# MotorCell.net
KiCad netlist of a schematic drawn in Altium Designer
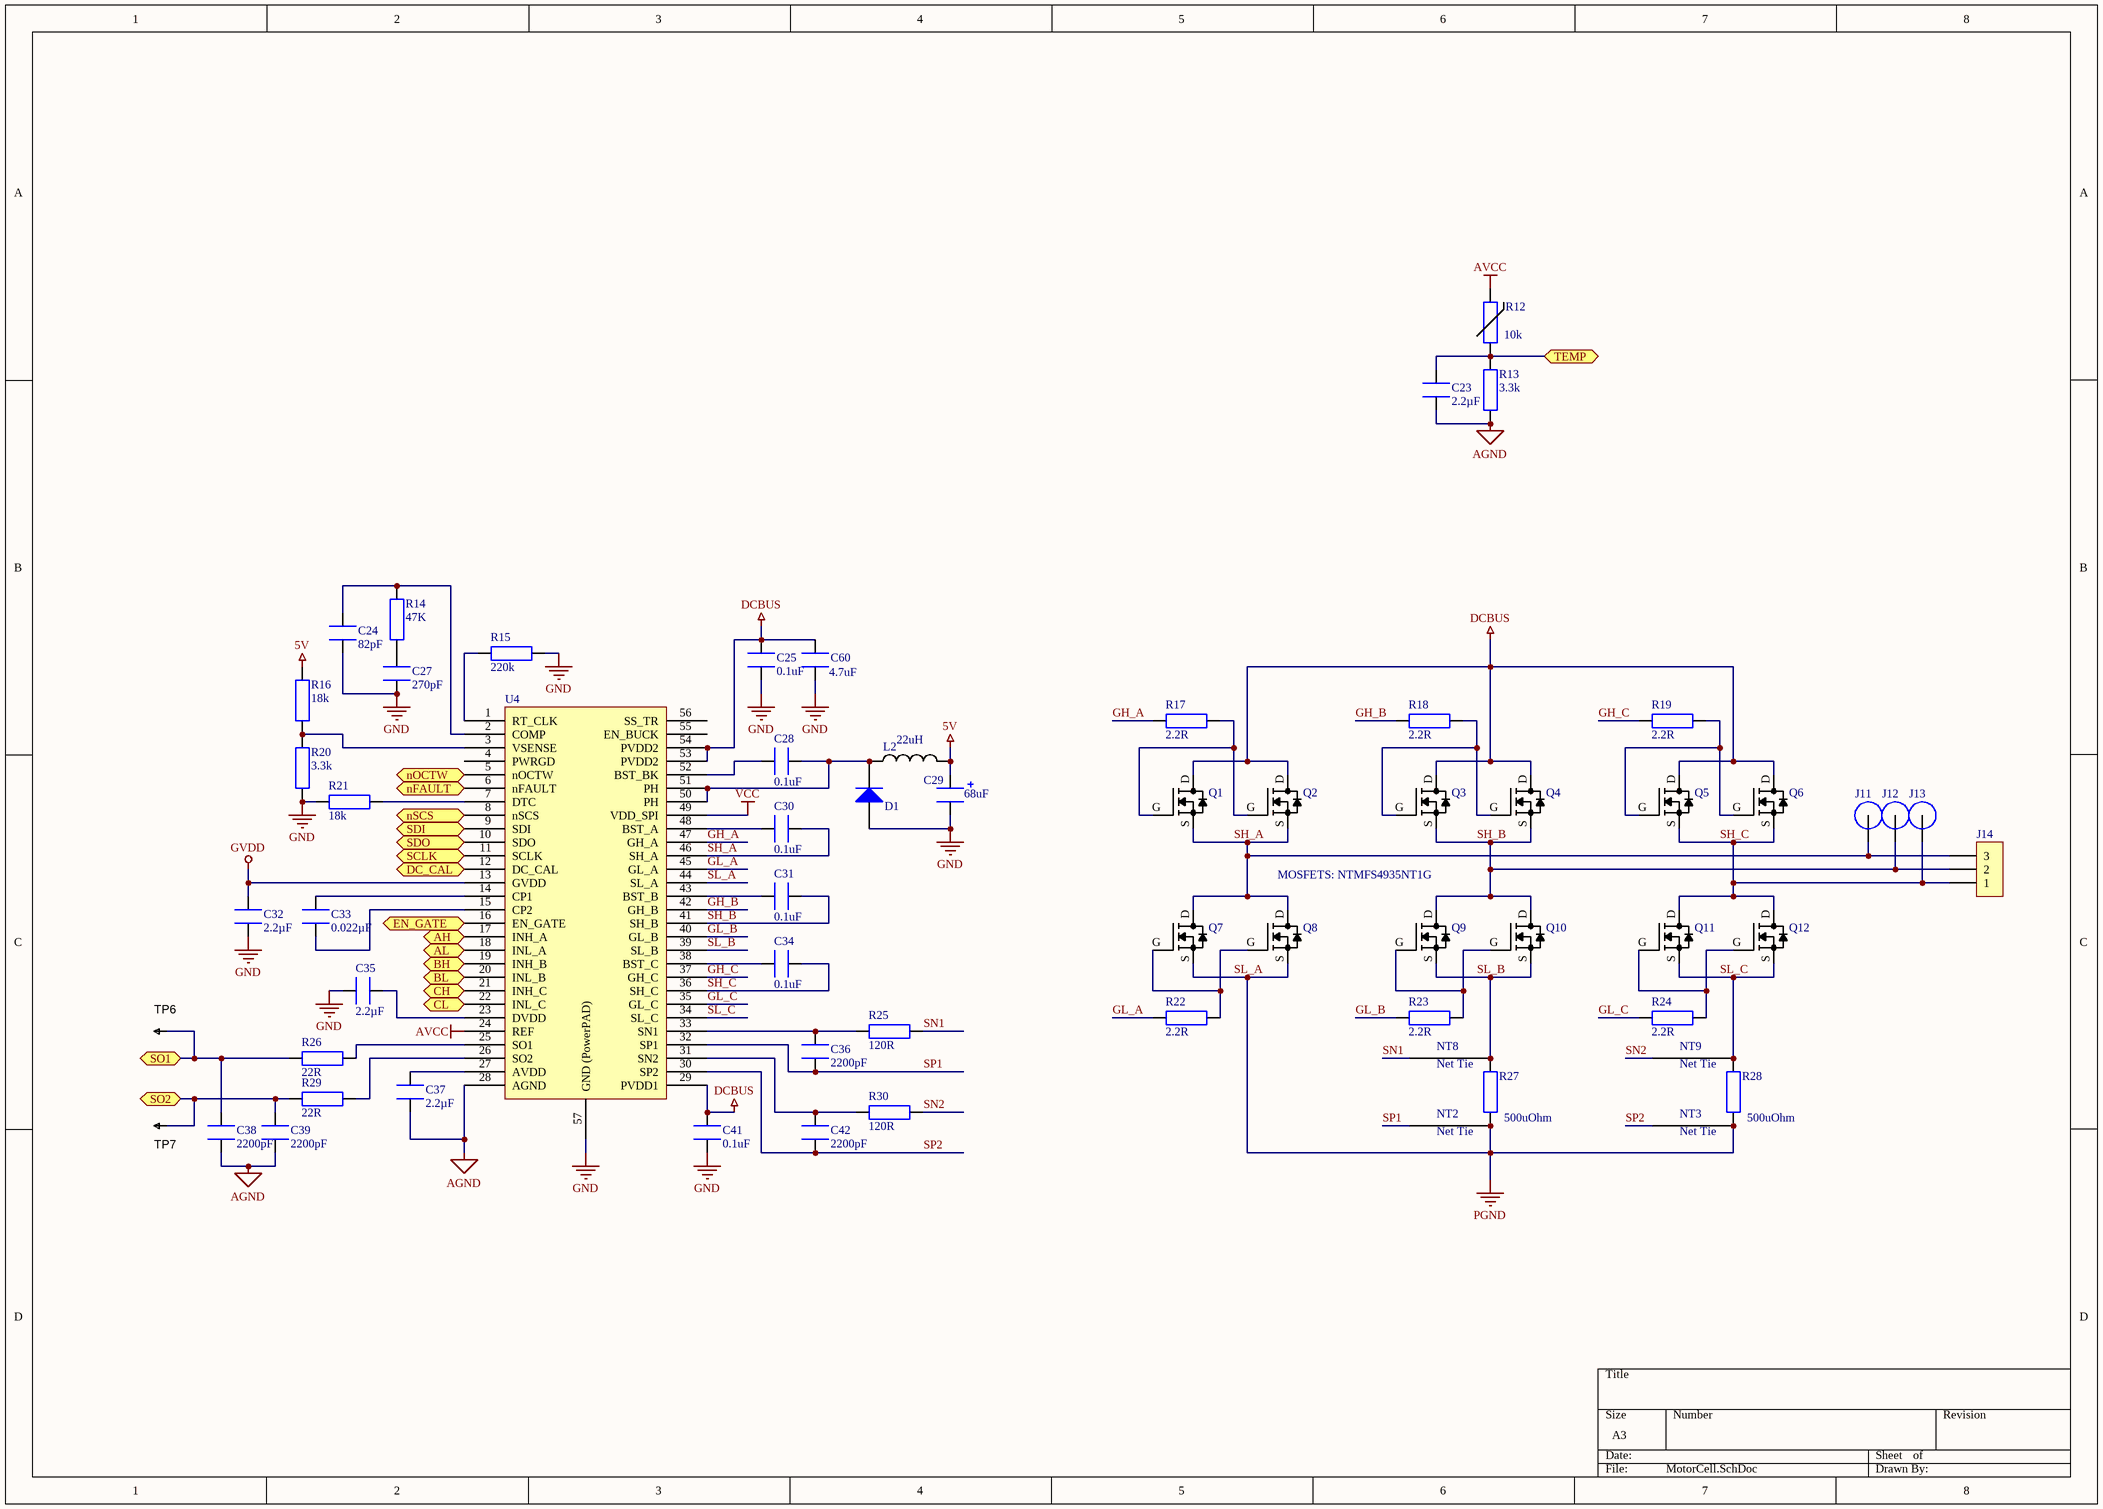
[diagram p0: MotorCell.SchDoc]

(export (version "E")
  (design (tool "Eeschema 10.0.6"))
  (components
    (comp (ref "C23")
      (value "2.2µF")
      (footprint "CAPC1608X09L")
      (description "CAP CER 2.2UF 16V X5R 0603")
      (fields
        (field (name "MANUFACTURER") "Murata Electronics North America")
        (field (name "MANUFACTURER PART NUMBER") "GRM188R61C225KE15D")
      )
      (libsource (lib "CustomComponents") (part "GRM188R61C225KE15D"))
    )
    (comp (ref "C24")
      (value "82pF")
      (footprint "CAPC1608X09L")
      (description "CAP CER 82PF 100V NP0 0603")
      (fields
        (field (name "MANUFACTURER") "Murata Electronics North America")
        (field (name "MANUFACTURER PART NUMBER") "GRM1885C2A820JA01D")
      )
      (libsource (lib "CustomComponents") (part "GRM1885C2A820JA01D"))
    )
    (comp (ref "C25")
      (value "0.1uF")
      (footprint "CAPC1608X09L")
      (description "CAP CER 0.1UF 50V X7R 0603")
      (fields
        (field (name "MANUFACTURER") "Murata Electronics North America")
        (field (name "MANUFACTURER PART NUMBER") "GRM188R71H104KA93D")
      )
      (libsource (lib "CustomComponents") (part "GRM188R71H104KA93D"))
    )
    (comp (ref "C27")
      (value "270pF")
      (footprint "CAPC1608X09L")
      (description "CAP CER 270PF 50V NP0 0603")
      (fields
        (field (name "MANUFACTURER") "Murata Electronics North America")
        (field (name "MANUFACTURER PART NUMBER") "GRM1885C1H271JA01D")
      )
      (libsource (lib "CustomComponents") (part "GRM1885C1H271JA01D"))
    )
    (comp (ref "C28")
      (value "0.1uF")
      (footprint "CAPC1608X09L")
      (description "CAP CER 0.1UF 50V X7R 0603")
      (fields
        (field (name "MANUFACTURER") "Murata Electronics North America")
        (field (name "MANUFACTURER PART NUMBER") "GRM188R71H104KA93D")
      )
      (libsource (lib "CustomComponents") (part "GRM188R71H104KA93D"))
    )
    (comp (ref "C29")
      (value "68uF")
      (footprint "CAPCP6032X28N")
      (description "CAP TANT 68UF 16V 20% 2312 250mOhm")
      (fields (field (name "MANUFACTURER") "KEMET") (field (name "TOLERANCE") "±20%"))
      (libsource (lib "CustomComponents") (part "T495C686M016ATE250"))
    )
    (comp (ref "C30")
      (value "0.1uF")
      (footprint "CAPC1608X09L")
      (description "CAP CER 0.1UF 50V X7R 0603")
      (fields
        (field (name "MANUFACTURER") "Murata Electronics North America")
        (field (name "MANUFACTURER PART NUMBER") "GRM188R71H104KA93D")
      )
      (libsource (lib "CustomComponents") (part "GRM188R71H104KA93D"))
    )
    (comp (ref "C31")
      (value "0.1uF")
      (footprint "CAPC1608X09L")
      (description "CAP CER 0.1UF 50V X7R 0603")
      (fields
        (field (name "MANUFACTURER") "Murata Electronics North America")
        (field (name "MANUFACTURER PART NUMBER") "GRM188R71H104KA93D")
      )
      (libsource (lib "CustomComponents") (part "GRM188R71H104KA93D"))
    )
    (comp (ref "C32")
      (value "2.2µF")
      (footprint "CAPC1608X09L")
      (description "CAP CER 2.2UF 16V X5R 0603")
      (fields
        (field (name "MANUFACTURER") "Murata Electronics North America")
        (field (name "MANUFACTURER PART NUMBER") "GRM188R61C225KE15D")
      )
      (libsource (lib "CustomComponents") (part "GRM188R61C225KE15D"))
    )
    (comp (ref "C33")
      (value "0.022µF")
      (footprint "CAPC1608X09L")
      (description "CAP CER 0.022UF 50V X7R 0603")
      (fields
        (field (name "MANUFACTURER") "Murata Electronics North America")
        (field (name "MANUFACTURER PART NUMBER") "GRM188R71H223KA01D")
      )
      (libsource (lib "CustomComponents") (part "GRM188R71H223KA01D"))
    )
    (comp (ref "C34")
      (value "0.1uF")
      (footprint "CAPC1608X09L")
      (description "CAP CER 0.1UF 50V X7R 0603")
      (fields
        (field (name "MANUFACTURER") "Murata Electronics North America")
        (field (name "MANUFACTURER PART NUMBER") "GRM188R71H104KA93D")
      )
      (libsource (lib "CustomComponents") (part "GRM188R71H104KA93D"))
    )
    (comp (ref "C35")
      (value "2.2µF")
      (footprint "CAPC1608X09L")
      (description "CAP CER 2.2UF 16V X5R 0603")
      (fields
        (field (name "MANUFACTURER") "Murata Electronics North America")
        (field (name "MANUFACTURER PART NUMBER") "GRM188R61C225KE15D")
      )
      (libsource (lib "CustomComponents") (part "GRM188R61C225KE15D"))
    )
    (comp (ref "C36")
      (value "2200pF")
      (footprint "CAPC1608X09L")
      (description "CAP CER 2200PF 50V NP0 0603")
      (fields
        (field (name "MANUFACTURER") "Murata Electronics North America")
        (field (name "TOLERANCE") "±5%")
      )
      (libsource (lib "CustomComponents") (part "GRM1885C1H222JA01D"))
    )
    (comp (ref "C37")
      (value "2.2µF")
      (footprint "CAPC1608X09L")
      (description "CAP CER 2.2UF 16V X5R 0603")
      (fields
        (field (name "MANUFACTURER") "Murata Electronics North America")
        (field (name "MANUFACTURER PART NUMBER") "GRM188R61C225KE15D")
      )
      (libsource (lib "CustomComponents") (part "GRM188R61C225KE15D"))
    )
    (comp (ref "C38")
      (value "2200pF")
      (footprint "CAPC1608X09L")
      (description "CAP CER 2200PF 50V NP0 0603")
      (fields
        (field (name "MANUFACTURER") "Murata Electronics North America")
        (field (name "TOLERANCE") "±5%")
      )
      (libsource (lib "CustomComponents") (part "GRM1885C1H222JA01D"))
    )
    (comp (ref "C39")
      (value "2200pF")
      (footprint "CAPC1608X09L")
      (description "CAP CER 2200PF 50V NP0 0603")
      (fields
        (field (name "MANUFACTURER") "Murata Electronics North America")
        (field (name "TOLERANCE") "±5%")
      )
      (libsource (lib "CustomComponents") (part "GRM1885C1H222JA01D"))
    )
    (comp (ref "C41")
      (value "0.1uF")
      (footprint "CAPC1608X09L")
      (description "CAP CER 0.1UF 50V X7R 0603")
      (fields
        (field (name "MANUFACTURER") "Murata Electronics North America")
        (field (name "MANUFACTURER PART NUMBER") "GRM188R71H104KA93D")
      )
      (libsource (lib "CustomComponents") (part "GRM188R71H104KA93D"))
    )
    (comp (ref "C42")
      (value "2200pF")
      (footprint "CAPC1608X09L")
      (description "CAP CER 2200PF 50V NP0 0603")
      (fields
        (field (name "MANUFACTURER") "Murata Electronics North America")
        (field (name "TOLERANCE") "±5%")
      )
      (libsource (lib "CustomComponents") (part "GRM1885C1H222JA01D"))
    )
    (comp (ref "C60")
      (value "4.7uF")
      (footprint "CAPC2012X09N")
      (description "CAP CER 4.7UF 35V X5R 0805")
      (fields
        (field (name "MANUFACTURER") "Murata Electronics North America")
        (field (name "TOLERANCE") "±10%")
      )
      (libsource (lib "CustomComponents") (part "GRM219R6YA475KA73D"))
    )
    (comp (ref "D1")
      (value "~")
      (footprint "DIOM2717X10N")
      (description "Rectifier Diode, Single, 40 V, 1 A, SOD-123FL, 2, 550 mV")
      (libsource (lib "CustomComponents") (part "MBR140SFT1G"))
    )
    (comp (ref "J11")
      (value "~")
      (footprint "M3 Spade Hole")
      (description "M3 Spade Terminal")
      (libsource (lib "CustomComponents") (part "M3 Spade Terminal"))
    )
    (comp (ref "J12")
      (value "~")
      (footprint "M3 Spade Hole")
      (description "M3 Spade Terminal")
      (libsource (lib "CustomComponents") (part "M3 Spade Terminal"))
    )
    (comp (ref "J13")
      (value "~")
      (footprint "M3 Spade Hole")
      (description "M3 Spade Terminal")
      (libsource (lib "CustomComponents") (part "M3 Spade Terminal"))
    )
    (comp (ref "J14")
      (value "1704936")
      (footprint "1704936")
      (description "CONN TERM BLOCK 3POS 7.62MM")
      (fields (field (name "MANUFACTURER") "Phoenix Contact") (field (name "VOLTAGE") "300V"))
      (libsource (lib "CustomComponents") (part "1704936"))
    )
    (comp (ref "L2")
      (value "22uH")
      (footprint "INDC6060X28N")
      (description "INDUCTOR 22UH 1.4A 175.5 MOHM")
      (libsource (lib "CustomComponents") (part "NR6028T220M"))
    )
    (comp (ref "NT2")
      (value "0.25mm")
      (footprint "NetTie_0.25mm")
      (libsource (lib "CustomComponents") (part "NetTie_0.25mm"))
    )
    (comp (ref "NT3")
      (value "0.25mm")
      (footprint "NetTie_0.25mm")
      (libsource (lib "CustomComponents") (part "NetTie_0.25mm"))
    )
    (comp (ref "NT8")
      (value "0.25mm")
      (footprint "NetTie_0.25mm")
      (libsource (lib "CustomComponents") (part "NetTie_0.25mm"))
    )
    (comp (ref "NT9")
      (value "0.25mm")
      (footprint "NetTie_0.25mm")
      (libsource (lib "CustomComponents") (part "NetTie_0.25mm"))
    )
    (comp (ref "Q1")
      (value "~")
      (footprint "SO8FL")
      (description "MOSFET N-CH 30V 13A SO8FL")
      (fields
        (field (name "MANUFACTURER") "ON Semiconductor")
        (field (name "MANUFACTURER PART NUMBER") "NTMFS4935NT1G")
      )
      (libsource (lib "CustomComponents") (part "NTMFS4935NT1G"))
    )
    (comp (ref "Q2")
      (value "FILL_FOOTPRINT")
      (footprint "SO8FL_FILL")
      (description "MOSFET N-CH 30V 13A SO8FL")
      (fields
        (field (name "MANUFACTURER") "ON Semiconductor")
        (field (name "MANUFACTURER PART NUMBER") "NTMFS4935NT1G")
      )
      (libsource (lib "CustomComponents") (part "NTMFS4935NT1G"))
    )
    (comp (ref "Q3")
      (value "~")
      (footprint "SO8FL")
      (description "MOSFET N-CH 30V 13A SO8FL")
      (fields
        (field (name "MANUFACTURER") "ON Semiconductor")
        (field (name "MANUFACTURER PART NUMBER") "NTMFS4935NT1G")
      )
      (libsource (lib "CustomComponents") (part "NTMFS4935NT1G"))
    )
    (comp (ref "Q4")
      (value "FILL_FOOTPRINT")
      (footprint "SO8FL_FILL")
      (description "MOSFET N-CH 30V 13A SO8FL")
      (fields
        (field (name "MANUFACTURER") "ON Semiconductor")
        (field (name "MANUFACTURER PART NUMBER") "NTMFS4935NT1G")
      )
      (libsource (lib "CustomComponents") (part "NTMFS4935NT1G"))
    )
    (comp (ref "Q5")
      (value "~")
      (footprint "SO8FL")
      (description "MOSFET N-CH 30V 13A SO8FL")
      (fields
        (field (name "MANUFACTURER") "ON Semiconductor")
        (field (name "MANUFACTURER PART NUMBER") "NTMFS4935NT1G")
      )
      (libsource (lib "CustomComponents") (part "NTMFS4935NT1G"))
    )
    (comp (ref "Q6")
      (value "FILL_FOOTPRINT")
      (footprint "SO8FL_FILL")
      (description "MOSFET N-CH 30V 13A SO8FL")
      (fields
        (field (name "MANUFACTURER") "ON Semiconductor")
        (field (name "MANUFACTURER PART NUMBER") "NTMFS4935NT1G")
      )
      (libsource (lib "CustomComponents") (part "NTMFS4935NT1G"))
    )
    (comp (ref "Q7")
      (value "~")
      (footprint "SO8FL")
      (description "MOSFET N-CH 30V 13A SO8FL")
      (fields
        (field (name "MANUFACTURER") "ON Semiconductor")
        (field (name "MANUFACTURER PART NUMBER") "NTMFS4935NT1G")
      )
      (libsource (lib "CustomComponents") (part "NTMFS4935NT1G"))
    )
    (comp (ref "Q8")
      (value "~")
      (footprint "SO8FL")
      (description "MOSFET N-CH 30V 13A SO8FL")
      (fields
        (field (name "MANUFACTURER") "ON Semiconductor")
        (field (name "MANUFACTURER PART NUMBER") "NTMFS4935NT1G")
      )
      (libsource (lib "CustomComponents") (part "NTMFS4935NT1G"))
    )
    (comp (ref "Q9")
      (value "~")
      (footprint "SO8FL")
      (description "MOSFET N-CH 30V 13A SO8FL")
      (fields
        (field (name "MANUFACTURER") "ON Semiconductor")
        (field (name "MANUFACTURER PART NUMBER") "NTMFS4935NT1G")
      )
      (libsource (lib "CustomComponents") (part "NTMFS4935NT1G"))
    )
    (comp (ref "Q10")
      (value "~")
      (footprint "SO8FL")
      (description "MOSFET N-CH 30V 13A SO8FL")
      (fields
        (field (name "MANUFACTURER") "ON Semiconductor")
        (field (name "MANUFACTURER PART NUMBER") "NTMFS4935NT1G")
      )
      (libsource (lib "CustomComponents") (part "NTMFS4935NT1G"))
    )
    (comp (ref "Q11")
      (value "~")
      (footprint "SO8FL")
      (description "MOSFET N-CH 30V 13A SO8FL")
      (fields
        (field (name "MANUFACTURER") "ON Semiconductor")
        (field (name "MANUFACTURER PART NUMBER") "NTMFS4935NT1G")
      )
      (libsource (lib "CustomComponents") (part "NTMFS4935NT1G"))
    )
    (comp (ref "Q12")
      (value "~")
      (footprint "SO8FL")
      (description "MOSFET N-CH 30V 13A SO8FL")
      (fields
        (field (name "MANUFACTURER") "ON Semiconductor")
        (field (name "MANUFACTURER PART NUMBER") "NTMFS4935NT1G")
      )
      (libsource (lib "CustomComponents") (part "NTMFS4935NT1G"))
    )
    (comp (ref "R12")
      (value "10k")
      (footprint "RESC1005X40N")
      (description "THERMISTOR 10K OHM NTC 0402 SMD")
      (libsource (lib "CustomComponents") (part "NCP15XH103F03RC"))
    )
    (comp (ref "R13")
      (value "3.3k")
      (footprint "RESC1608X55N")
      (description "RES SMD 3.3K OHM 1% 1/10W 0603")
      (fields
        (field (name "MANUFACTURER") "Yageo")
        (field (name "MANUFACTURER PART NUMBER") "RC0603FR-073K3L")
      )
      (libsource (lib "CustomComponents") (part "RC0603FR-073K3L"))
    )
    (comp (ref "R14")
      (value "47K")
      (footprint "RESC1608X55N")
      (description "RES SMD 47K OHM 1% 1/10W 0603")
      (fields
        (field (name "MANUFACTURER") "Yageo")
        (field (name "MANUFACTURER PART NUMBER") "RC0603FR-0747KL")
      )
      (libsource (lib "CustomComponents") (part "RC0603FR-0747KL"))
    )
    (comp (ref "R15")
      (value "220k")
      (footprint "RESC1608X55N")
      (description "RES SMD 220K OHM 1% 1/10W 0603")
      (fields
        (field (name "MANUFACTURER") "Yageo")
        (field (name "MANUFACTURER PART NUMBER") "RC0603FR-07220KL")
      )
      (libsource (lib "CustomComponents") (part "RC0603FR-07220KL"))
    )
    (comp (ref "R16")
      (value "18k")
      (footprint "RESC1608X55N")
      (description "RES SMD 18K OHM 1% 1/10W 0603")
      (fields
        (field (name "MANUFACTURER") "Yageo")
        (field (name "MANUFACTURER PART NUMBER") "RC0603FR-0718KL")
      )
      (libsource (lib "CustomComponents") (part "RC0603FR-0718KL"))
    )
    (comp (ref "R17")
      (value "2.2R")
      (footprint "RESC1608X55N")
      (description "RES SMD 2.2 OHM 1% 1/10W 0603")
      (fields
        (field (name "MANUFACTURER") "Yageo")
        (field (name "MANUFACTURER PART NUMBER") "RC0603FR-072R2L")
      )
      (libsource (lib "CustomComponents") (part "RC0603FR-072R2L"))
    )
    (comp (ref "R18")
      (value "2.2R")
      (footprint "RESC1608X55N")
      (description "RES SMD 2.2 OHM 1% 1/10W 0603")
      (fields
        (field (name "MANUFACTURER") "Yageo")
        (field (name "MANUFACTURER PART NUMBER") "RC0603FR-072R2L")
      )
      (libsource (lib "CustomComponents") (part "RC0603FR-072R2L"))
    )
    (comp (ref "R19")
      (value "2.2R")
      (footprint "RESC1608X55N")
      (description "RES SMD 2.2 OHM 1% 1/10W 0603")
      (fields
        (field (name "MANUFACTURER") "Yageo")
        (field (name "MANUFACTURER PART NUMBER") "RC0603FR-072R2L")
      )
      (libsource (lib "CustomComponents") (part "RC0603FR-072R2L"))
    )
    (comp (ref "R20")
      (value "3.3k")
      (footprint "RESC1608X55N")
      (description "RES SMD 3.3K OHM 1% 1/10W 0603")
      (fields
        (field (name "MANUFACTURER") "Yageo")
        (field (name "MANUFACTURER PART NUMBER") "RC0603FR-073K3L")
      )
      (libsource (lib "CustomComponents") (part "RC0603FR-073K3L"))
    )
    (comp (ref "R21")
      (value "18k")
      (footprint "RESC1608X55N")
      (description "RES SMD 18K OHM 1% 1/10W 0603")
      (fields
        (field (name "MANUFACTURER") "Yageo")
        (field (name "MANUFACTURER PART NUMBER") "RC0603FR-0718KL")
      )
      (libsource (lib "CustomComponents") (part "RC0603FR-0718KL"))
    )
    (comp (ref "R22")
      (value "2.2R")
      (footprint "RESC1608X55N")
      (description "RES SMD 2.2 OHM 1% 1/10W 0603")
      (fields
        (field (name "MANUFACTURER") "Yageo")
        (field (name "MANUFACTURER PART NUMBER") "RC0603FR-072R2L")
      )
      (libsource (lib "CustomComponents") (part "RC0603FR-072R2L"))
    )
    (comp (ref "R23")
      (value "2.2R")
      (footprint "RESC1608X55N")
      (description "RES SMD 2.2 OHM 1% 1/10W 0603")
      (fields
        (field (name "MANUFACTURER") "Yageo")
        (field (name "MANUFACTURER PART NUMBER") "RC0603FR-072R2L")
      )
      (libsource (lib "CustomComponents") (part "RC0603FR-072R2L"))
    )
    (comp (ref "R24")
      (value "2.2R")
      (footprint "RESC1608X55N")
      (description "RES SMD 2.2 OHM 1% 1/10W 0603")
      (fields
        (field (name "MANUFACTURER") "Yageo")
        (field (name "MANUFACTURER PART NUMBER") "RC0603FR-072R2L")
      )
      (libsource (lib "CustomComponents") (part "RC0603FR-072R2L"))
    )
    (comp (ref "R25")
      (value "120R")
      (footprint "RESC1608X55N")
      (description "RES SMD 120 OHM 1% 1/10W 0603")
      (fields
        (field (name "MANUFACTURER") "Yageo")
        (field (name "MANUFACTURER PART NUMBER") "RC0603FR-07120RL")
      )
      (libsource (lib "CustomComponents") (part "RC0603FR-07120RL"))
    )
    (comp (ref "R26")
      (value "22R")
      (footprint "RESC1608X55N")
      (description "RES SMD 22 OHM 1% 1/10W 0603")
      (fields
        (field (name "MANUFACTURER") "Yageo")
        (field (name "MANUFACTURER PART NUMBER") "RC0603FR-0722RL")
      )
      (libsource (lib "CustomComponents") (part "RC0603FR-0722RL"))
    )
    (comp (ref "R27")
      (value "500uOhm")
      (footprint "RESC6432X09N")
      (description "RES SMD 0.0005 OHM 1% 3W 2512")
      (fields (field (name "MANUFACTURER") "Riedon") (field (name "TOLERANCE") "±1%"))
      (libsource (lib "CustomComponents") (part "CSR2512C0R0005F"))
    )
    (comp (ref "R28")
      (value "500uOhm")
      (footprint "RESC6432X09N")
      (description "RES SMD 0.0005 OHM 1% 3W 2512")
      (fields (field (name "MANUFACTURER") "Riedon") (field (name "TOLERANCE") "±1%"))
      (libsource (lib "CustomComponents") (part "CSR2512C0R0005F"))
    )
    (comp (ref "R29")
      (value "22R")
      (footprint "RESC1608X55N")
      (description "RES SMD 22 OHM 1% 1/10W 0603")
      (fields
        (field (name "MANUFACTURER") "Yageo")
        (field (name "MANUFACTURER PART NUMBER") "RC0603FR-0722RL")
      )
      (libsource (lib "CustomComponents") (part "RC0603FR-0722RL"))
    )
    (comp (ref "R30")
      (value "120R")
      (footprint "RESC1608X55N")
      (description "RES SMD 120 OHM 1% 1/10W 0603")
      (fields
        (field (name "MANUFACTURER") "Yageo")
        (field (name "MANUFACTURER PART NUMBER") "RC0603FR-07120RL")
      )
      (libsource (lib "CustomComponents") (part "RC0603FR-07120RL"))
    )
    (comp (ref "TP6")
      (value "TESTPOINT")
      (footprint "TP-R30")
      (description "SMD test pin")
      (libsource (lib "PBL - Test Points") (part "TESTPOINT"))
    )
    (comp (ref "TP7")
      (value "TESTPOINT")
      (footprint "TP-R30")
      (description "SMD test pin")
      (libsource (lib "PBL - Test Points") (part "TESTPOINT"))
    )
    (comp (ref "U4")
      (value "~")
      (footprint "TSSOP50P810X120_HS-57N")
      (description "MOTOR DRIVER, 3PH, 56HTSSOP")
      (libsource (lib "CustomComponents") (part "DRV8301"))
    )
  )
  (nets
    (net (code "1") (name "/AH") (class "Default")
      (node (ref "U4") (pin "17") (pinfunction "INH_A_17") (pintype "passive"))
    )
    (net (code "2") (name "/AL") (class "Default")
      (node (ref "U4") (pin "18") (pinfunction "INL_A_18") (pintype "passive"))
    )
    (net (code "3") (name "/BH") (class "Default")
      (node (ref "U4") (pin "19") (pinfunction "INH_B_19") (pintype "passive"))
    )
    (net (code "4") (name "/BL") (class "Default")
      (node (ref "U4") (pin "20") (pinfunction "INL_B_20") (pintype "passive"))
    )
    (net (code "5") (name "/CH") (class "Default")
      (node (ref "U4") (pin "21") (pinfunction "INH_C_21") (pintype "passive"))
    )
    (net (code "6") (name "/CL") (class "Default")
      (node (ref "U4") (pin "22") (pinfunction "INL_C_22") (pintype "passive"))
    )
    (net (code "7") (name "/DC_CAL") (class "Default")
      (node (ref "U4") (pin "12") (pinfunction "DC_CAL_12") (pintype "passive"))
    )
    (net (code "8") (name "/EN_GATE") (class "Default")
      (node (ref "U4") (pin "16") (pinfunction "EN_GATE_16") (pintype "passive"))
    )
    (net (code "9") (name "/GH_A") (class "Default")
      (node (ref "R17") (pin "2") (pinfunction "0_2") (pintype "passive"))
      (node (ref "U4") (pin "47") (pinfunction "GH_A_47") (pintype "passive"))
    )
    (net (code "10") (name "/GH_B") (class "Default")
      (node (ref "R18") (pin "2") (pinfunction "0_2") (pintype "passive"))
      (node (ref "U4") (pin "42") (pinfunction "GH_B_42") (pintype "passive"))
    )
    (net (code "11") (name "/GH_C") (class "Default")
      (node (ref "R19") (pin "2") (pinfunction "0_2") (pintype "passive"))
      (node (ref "U4") (pin "37") (pinfunction "GH_C_37") (pintype "passive"))
    )
    (net (code "12") (name "/GL_A") (class "Default")
      (node (ref "R22") (pin "2") (pinfunction "0_2") (pintype "passive"))
      (node (ref "U4") (pin "45") (pinfunction "GL_A_45") (pintype "passive"))
    )
    (net (code "13") (name "/GL_B") (class "Default")
      (node (ref "R23") (pin "2") (pinfunction "0_2") (pintype "passive"))
      (node (ref "U4") (pin "40") (pinfunction "GL_B_40") (pintype "passive"))
    )
    (net (code "14") (name "/GL_C") (class "Default")
      (node (ref "R24") (pin "2") (pinfunction "0_2") (pintype "passive"))
      (node (ref "U4") (pin "35") (pinfunction "GL_C_35") (pintype "passive"))
    )
    (net (code "15") (name "/SCLK") (class "Default")
      (node (ref "U4") (pin "11") (pinfunction "SCLK_11") (pintype "passive"))
    )
    (net (code "16") (name "/SDI") (class "Default")
      (node (ref "U4") (pin "9") (pinfunction "SDI_9") (pintype "passive"))
    )
    (net (code "17") (name "/SDO") (class "Default")
      (node (ref "U4") (pin "10") (pinfunction "SDO_10") (pintype "passive"))
    )
    (net (code "18") (name "/SH_A") (class "Default")
      (node (ref "C30") (pin "1") (pinfunction "1_1") (pintype "passive"))
      (node (ref "J11") (pin "1") (pinfunction "1_1") (pintype "passive"))
      (node (ref "J14") (pin "3") (pinfunction "3_3") (pintype "passive"))
      (node (ref "Q1") (pin "S") (pinfunction "S_S") (pintype "passive"))
      (node (ref "Q2") (pin "S") (pinfunction "S_S") (pintype "passive"))
      (node (ref "Q7") (pin "D") (pinfunction "D_D") (pintype "passive"))
      (node (ref "Q8") (pin "D") (pinfunction "D_D") (pintype "passive"))
      (node (ref "U4") (pin "46") (pinfunction "SH_A_46") (pintype "passive"))
    )
    (net (code "19") (name "/SH_B") (class "Default")
      (node (ref "C31") (pin "1") (pinfunction "1_1") (pintype "passive"))
      (node (ref "J12") (pin "1") (pinfunction "1_1") (pintype "passive"))
      (node (ref "J14") (pin "2") (pinfunction "2_2") (pintype "passive"))
      (node (ref "Q10") (pin "D") (pinfunction "D_D") (pintype "passive"))
      (node (ref "Q3") (pin "S") (pinfunction "S_S") (pintype "passive"))
      (node (ref "Q4") (pin "S") (pinfunction "S_S") (pintype "passive"))
      (node (ref "Q9") (pin "D") (pinfunction "D_D") (pintype "passive"))
      (node (ref "U4") (pin "41") (pinfunction "SH_B_41") (pintype "passive"))
    )
    (net (code "20") (name "/SH_C") (class "Default")
      (node (ref "C34") (pin "1") (pinfunction "1_1") (pintype "passive"))
      (node (ref "J13") (pin "1") (pinfunction "1_1") (pintype "passive"))
      (node (ref "J14") (pin "1") (pinfunction "1_1") (pintype "passive"))
      (node (ref "Q11") (pin "D") (pinfunction "D_D") (pintype "passive"))
      (node (ref "Q12") (pin "D") (pinfunction "D_D") (pintype "passive"))
      (node (ref "Q5") (pin "S") (pinfunction "S_S") (pintype "passive"))
      (node (ref "Q6") (pin "S") (pinfunction "S_S") (pintype "passive"))
      (node (ref "U4") (pin "36") (pinfunction "SH_C_36") (pintype "passive"))
    )
    (net (code "21") (name "/SL_B") (class "Default")
      (node (ref "NT8") (pin "2") (pintype "passive"))
      (node (ref "Q10") (pin "S") (pinfunction "S_S") (pintype "passive"))
      (node (ref "Q9") (pin "S") (pinfunction "S_S") (pintype "passive"))
      (node (ref "R27") (pin "2") (pinfunction "0_2") (pintype "passive"))
      (node (ref "U4") (pin "39") (pinfunction "SL_B_39") (pintype "passive"))
    )
    (net (code "22") (name "/SL_C") (class "Default")
      (node (ref "NT9") (pin "2") (pintype "passive"))
      (node (ref "Q11") (pin "S") (pinfunction "S_S") (pintype "passive"))
      (node (ref "Q12") (pin "S") (pinfunction "S_S") (pintype "passive"))
      (node (ref "R28") (pin "2") (pinfunction "0_2") (pintype "passive"))
      (node (ref "U4") (pin "34") (pinfunction "SL_C_34") (pintype "passive"))
    )
    (net (code "23") (name "/SN1") (class "Default")
      (node (ref "NT8") (pin "1") (pintype "passive"))
      (node (ref "R25") (pin "1") (pinfunction "0_1") (pintype "passive"))
    )
    (net (code "24") (name "/SN2") (class "Default")
      (node (ref "NT9") (pin "1") (pintype "passive"))
      (node (ref "R30") (pin "1") (pinfunction "0_1") (pintype "passive"))
    )
    (net (code "25") (name "/SO1") (class "Default")
      (node (ref "C38") (pin "1") (pinfunction "1_1") (pintype "passive"))
      (node (ref "R26") (pin "2") (pinfunction "0_2") (pintype "passive"))
      (node (ref "TP6") (pin "1") (pintype "passive"))
    )
    (net (code "26") (name "/SO2") (class "Default")
      (node (ref "C39") (pin "1") (pinfunction "1_1") (pintype "passive"))
      (node (ref "R29") (pin "2") (pinfunction "0_2") (pintype "passive"))
      (node (ref "TP7") (pin "1") (pintype "passive"))
    )
    (net (code "27") (name "/SP1") (class "Default")
      (node (ref "C36") (pin "2") (pinfunction "2_2") (pintype "passive"))
      (node (ref "NT2") (pin "1") (pintype "passive"))
      (node (ref "U4") (pin "32") (pinfunction "SP1_32") (pintype "passive"))
    )
    (net (code "28") (name "/SP2") (class "Default")
      (node (ref "C42") (pin "2") (pinfunction "2_2") (pintype "passive"))
      (node (ref "NT3") (pin "1") (pintype "passive"))
      (node (ref "U4") (pin "30") (pinfunction "SP2_30") (pintype "passive"))
    )
    (net (code "29") (name "/TEMP") (class "Default")
      (node (ref "C23") (pin "2") (pinfunction "2_2") (pintype "passive"))
      (node (ref "R12") (pin "1") (pinfunction "0_1") (pintype "passive"))
      (node (ref "R13") (pin "1") (pinfunction "0_1") (pintype "passive"))
    )
    (net (code "30") (name "/nFAULT") (class "Default")
      (node (ref "U4") (pin "6") (pinfunction "nFAULT_6") (pintype "passive"))
    )
    (net (code "31") (name "/nOCTW") (class "Default")
      (node (ref "U4") (pin "5") (pinfunction "nOCTW_5") (pintype "passive"))
    )
    (net (code "32") (name "/nSCS") (class "Default")
      (node (ref "U4") (pin "8") (pinfunction "nSCS_8") (pintype "passive"))
    )
    (net (code "33") (name "5V") (class "Default")
      (node (ref "C29") (pin "1") (pinfunction "1_1") (pintype "passive"))
      (node (ref "L2") (pin "2") (pinfunction "2_2") (pintype "passive"))
      (node (ref "R16") (pin "1") (pinfunction "0_1") (pintype "passive"))
    )
    (net (code "34") (name "AGND") (class "Default")
      (node (ref "C23") (pin "1") (pinfunction "1_1") (pintype "passive"))
      (node (ref "C37") (pin "1") (pinfunction "1_1") (pintype "passive"))
      (node (ref "C38") (pin "2") (pinfunction "2_2") (pintype "passive"))
      (node (ref "C39") (pin "2") (pinfunction "2_2") (pintype "passive"))
      (node (ref "R13") (pin "2") (pinfunction "0_2") (pintype "passive"))
      (node (ref "U4") (pin "28") (pinfunction "AGND_28") (pintype "passive"))
    )
    (net (code "35") (name "AVCC") (class "Default")
      (node (ref "R12") (pin "2") (pinfunction "0_2") (pintype "passive"))
      (node (ref "U4") (pin "24") (pinfunction "REF_24") (pintype "passive"))
    )
    (net (code "36") (name "DCBUS") (class "Default")
      (node (ref "C25") (pin "1") (pinfunction "1_1") (pintype "passive"))
      (node (ref "C41") (pin "1") (pinfunction "1_1") (pintype "passive"))
      (node (ref "C60") (pin "2") (pinfunction "2_2") (pintype "passive"))
      (node (ref "Q1") (pin "D") (pinfunction "D_D") (pintype "passive"))
      (node (ref "Q2") (pin "D") (pinfunction "D_D") (pintype "passive"))
      (node (ref "Q3") (pin "D") (pinfunction "D_D") (pintype "passive"))
      (node (ref "Q4") (pin "D") (pinfunction "D_D") (pintype "passive"))
      (node (ref "Q5") (pin "D") (pinfunction "D_D") (pintype "passive"))
      (node (ref "Q6") (pin "D") (pinfunction "D_D") (pintype "passive"))
      (node (ref "U4") (pin "29") (pinfunction "PVDD1_29") (pintype "passive"))
      (node (ref "U4") (pin "53") (pinfunction "PVDD2_53") (pintype "passive"))
      (node (ref "U4") (pin "54") (pinfunction "PVDD2_54") (pintype "passive"))
    )
    (net (code "37") (name "GND") (class "Default")
      (node (ref "C24") (pin "2") (pinfunction "2_2") (pintype "passive"))
      (node (ref "C25") (pin "2") (pinfunction "2_2") (pintype "passive"))
      (node (ref "C27") (pin "2") (pinfunction "2_2") (pintype "passive"))
      (node (ref "C29") (pin "2") (pinfunction "2_2") (pintype "passive"))
      (node (ref "C32") (pin "1") (pinfunction "1_1") (pintype "passive"))
      (node (ref "C35") (pin "1") (pinfunction "1_1") (pintype "passive"))
      (node (ref "C41") (pin "2") (pinfunction "2_2") (pintype "passive"))
      (node (ref "C60") (pin "1") (pinfunction "1_1") (pintype "passive"))
      (node (ref "D1") (pin "A") (pinfunction "A_A") (pintype "passive"))
      (node (ref "R15") (pin "2") (pinfunction "0_2") (pintype "passive"))
      (node (ref "R20") (pin "2") (pinfunction "0_2") (pintype "passive"))
      (node (ref "R21") (pin "2") (pinfunction "0_2") (pintype "passive"))
      (node (ref "U4") (pin "57") (pinfunction "GND_(PowerPAD)_57") (pintype "passive"))
    )
    (net (code "38") (name "GVDD") (class "Default")
      (node (ref "C32") (pin "2") (pinfunction "2_2") (pintype "passive"))
      (node (ref "U4") (pin "13") (pinfunction "GVDD_13") (pintype "passive"))
    )
    (net (code "39") (name "Net-(C27-Pad1)") (class "Default")
      (node (ref "C27") (pin "1") (pinfunction "1_1") (pintype "passive"))
      (node (ref "R14") (pin "2") (pinfunction "0_2") (pintype "passive"))
    )
    (net (code "40") (name "Net-(C28-Pad1)") (class "Default")
      (node (ref "C28") (pin "1") (pinfunction "1_1") (pintype "passive"))
      (node (ref "D1") (pin "K") (pinfunction "K_K") (pintype "passive"))
      (node (ref "L2") (pin "1") (pinfunction "1_1") (pintype "passive"))
      (node (ref "U4") (pin "50") (pinfunction "PH_50") (pintype "passive"))
      (node (ref "U4") (pin "51") (pinfunction "PH_51") (pintype "passive"))
    )
    (net (code "41") (name "Net-(Q1-PadG)") (class "Default")
      (node (ref "Q1") (pin "G") (pinfunction "G_G") (pintype "passive"))
      (node (ref "Q2") (pin "G") (pinfunction "G_G") (pintype "passive"))
      (node (ref "R17") (pin "1") (pinfunction "0_1") (pintype "passive"))
    )
    (net (code "42") (name "Net-(Q3-PadG)") (class "Default")
      (node (ref "Q3") (pin "G") (pinfunction "G_G") (pintype "passive"))
      (node (ref "Q4") (pin "G") (pinfunction "G_G") (pintype "passive"))
      (node (ref "R18") (pin "1") (pinfunction "0_1") (pintype "passive"))
    )
    (net (code "43") (name "Net-(Q5-PadG)") (class "Default")
      (node (ref "Q5") (pin "G") (pinfunction "G_G") (pintype "passive"))
      (node (ref "Q6") (pin "G") (pinfunction "G_G") (pintype "passive"))
      (node (ref "R19") (pin "1") (pinfunction "0_1") (pintype "passive"))
    )
    (net (code "44") (name "Net-(Q7-PadG)") (class "Default")
      (node (ref "Q7") (pin "G") (pinfunction "G_G") (pintype "passive"))
      (node (ref "Q8") (pin "G") (pinfunction "G_G") (pintype "passive"))
      (node (ref "R22") (pin "1") (pinfunction "0_1") (pintype "passive"))
    )
    (net (code "45") (name "Net-(Q10-PadG)") (class "Default")
      (node (ref "Q10") (pin "G") (pinfunction "G_G") (pintype "passive"))
      (node (ref "Q9") (pin "G") (pinfunction "G_G") (pintype "passive"))
      (node (ref "R23") (pin "1") (pinfunction "0_1") (pintype "passive"))
    )
    (net (code "46") (name "Net-(Q11-PadG)") (class "Default")
      (node (ref "Q11") (pin "G") (pinfunction "G_G") (pintype "passive"))
      (node (ref "Q12") (pin "G") (pinfunction "G_G") (pintype "passive"))
      (node (ref "R24") (pin "1") (pinfunction "0_1") (pintype "passive"))
    )
    (net (code "47") (name "Net-(U4-AVDD)") (class "Default")
      (node (ref "C37") (pin "2") (pinfunction "2_2") (pintype "passive"))
      (node (ref "U4") (pin "27") (pinfunction "AVDD_27") (pintype "passive"))
    )
    (net (code "48") (name "Net-(U4-BST_A)") (class "Default")
      (node (ref "C30") (pin "2") (pinfunction "2_2") (pintype "passive"))
      (node (ref "U4") (pin "48") (pinfunction "BST_A_48") (pintype "passive"))
    )
    (net (code "49") (name "Net-(U4-BST_B)") (class "Default")
      (node (ref "C31") (pin "2") (pinfunction "2_2") (pintype "passive"))
      (node (ref "U4") (pin "43") (pinfunction "BST_B_43") (pintype "passive"))
    )
    (net (code "50") (name "Net-(U4-BST_BK)") (class "Default")
      (node (ref "C28") (pin "2") (pinfunction "2_2") (pintype "passive"))
      (node (ref "U4") (pin "52") (pinfunction "BST_BK_52") (pintype "passive"))
    )
    (net (code "51") (name "Net-(U4-BST_C)") (class "Default")
      (node (ref "C34") (pin "2") (pinfunction "2_2") (pintype "passive"))
      (node (ref "U4") (pin "38") (pinfunction "BST_C_38") (pintype "passive"))
    )
    (net (code "52") (name "Net-(U4-COMP)") (class "Default")
      (node (ref "C24") (pin "1") (pinfunction "1_1") (pintype "passive"))
      (node (ref "R14") (pin "1") (pinfunction "0_1") (pintype "passive"))
      (node (ref "U4") (pin "2") (pinfunction "COMP_2") (pintype "passive"))
    )
    (net (code "53") (name "Net-(U4-CP1)") (class "Default")
      (node (ref "C33") (pin "1") (pinfunction "1_1") (pintype "passive"))
      (node (ref "U4") (pin "14") (pinfunction "CP1_14") (pintype "passive"))
    )
    (net (code "54") (name "Net-(U4-CP2)") (class "Default")
      (node (ref "C33") (pin "2") (pinfunction "2_2") (pintype "passive"))
      (node (ref "U4") (pin "15") (pinfunction "CP2_15") (pintype "passive"))
    )
    (net (code "55") (name "Net-(U4-DTC)") (class "Default")
      (node (ref "R21") (pin "1") (pinfunction "0_1") (pintype "passive"))
      (node (ref "U4") (pin "7") (pinfunction "DTC_7") (pintype "passive"))
    )
    (net (code "56") (name "Net-(U4-DVDD)") (class "Default")
      (node (ref "C35") (pin "2") (pinfunction "2_2") (pintype "passive"))
      (node (ref "U4") (pin "23") (pinfunction "DVDD_23") (pintype "passive"))
    )
    (net (code "57") (name "Net-(U4-RT_CLK)") (class "Default")
      (node (ref "R15") (pin "1") (pinfunction "0_1") (pintype "passive"))
      (node (ref "U4") (pin "1") (pinfunction "RT_CLK_1") (pintype "passive"))
    )
    (net (code "58") (name "Net-(U4-SN1)") (class "Default")
      (node (ref "C36") (pin "1") (pinfunction "1_1") (pintype "passive"))
      (node (ref "R25") (pin "2") (pinfunction "0_2") (pintype "passive"))
      (node (ref "U4") (pin "33") (pinfunction "SN1_33") (pintype "passive"))
    )
    (net (code "59") (name "Net-(U4-SN2)") (class "Default")
      (node (ref "C42") (pin "1") (pinfunction "1_1") (pintype "passive"))
      (node (ref "R30") (pin "2") (pinfunction "0_2") (pintype "passive"))
      (node (ref "U4") (pin "31") (pinfunction "SN2_31") (pintype "passive"))
    )
    (net (code "60") (name "Net-(U4-SO1)") (class "Default")
      (node (ref "R26") (pin "1") (pinfunction "0_1") (pintype "passive"))
      (node (ref "U4") (pin "25") (pinfunction "SO1_25") (pintype "passive"))
    )
    (net (code "61") (name "Net-(U4-SO2)") (class "Default")
      (node (ref "R29") (pin "1") (pinfunction "0_1") (pintype "passive"))
      (node (ref "U4") (pin "26") (pinfunction "SO2_26") (pintype "passive"))
    )
    (net (code "62") (name "Net-(U4-VSENSE)") (class "Default")
      (node (ref "R16") (pin "2") (pinfunction "0_2") (pintype "passive"))
      (node (ref "R20") (pin "1") (pinfunction "0_1") (pintype "passive"))
      (node (ref "U4") (pin "3") (pinfunction "VSENSE_3") (pintype "passive"))
    )
    (net (code "63") (name "PGND") (class "Default")
      (node (ref "NT2") (pin "2") (pintype "passive"))
      (node (ref "NT3") (pin "2") (pintype "passive"))
      (node (ref "Q7") (pin "S") (pinfunction "S_S") (pintype "passive"))
      (node (ref "Q8") (pin "S") (pinfunction "S_S") (pintype "passive"))
      (node (ref "R27") (pin "1") (pinfunction "0_1") (pintype "passive"))
      (node (ref "R28") (pin "1") (pinfunction "0_1") (pintype "passive"))
      (node (ref "U4") (pin "44") (pinfunction "SL_A_44") (pintype "passive"))
    )
    (net (code "64") (name "VCC") (class "Default")
      (node (ref "U4") (pin "49") (pinfunction "VDD_SPI_49") (pintype "passive"))
    )
    (net (code "65") (name "unconnected-(U4-EN_BUCK-Pad55)") (class "Default")
      (node (ref "U4") (pin "55") (pinfunction "EN_BUCK_55") (pintype "passive"))
    )
    (net (code "66") (name "unconnected-(U4-PWRGD-Pad4)") (class "Default")
      (node (ref "U4") (pin "4") (pinfunction "PWRGD_4") (pintype "passive"))
    )
    (net (code "67") (name "unconnected-(U4-SS_TR-Pad56)") (class "Default")
      (node (ref "U4") (pin "56") (pinfunction "SS_TR_56") (pintype "passive"))
    )
  )
)
